# asincronico.net
KiCad netlist of a schematic drawn in Altium Designer
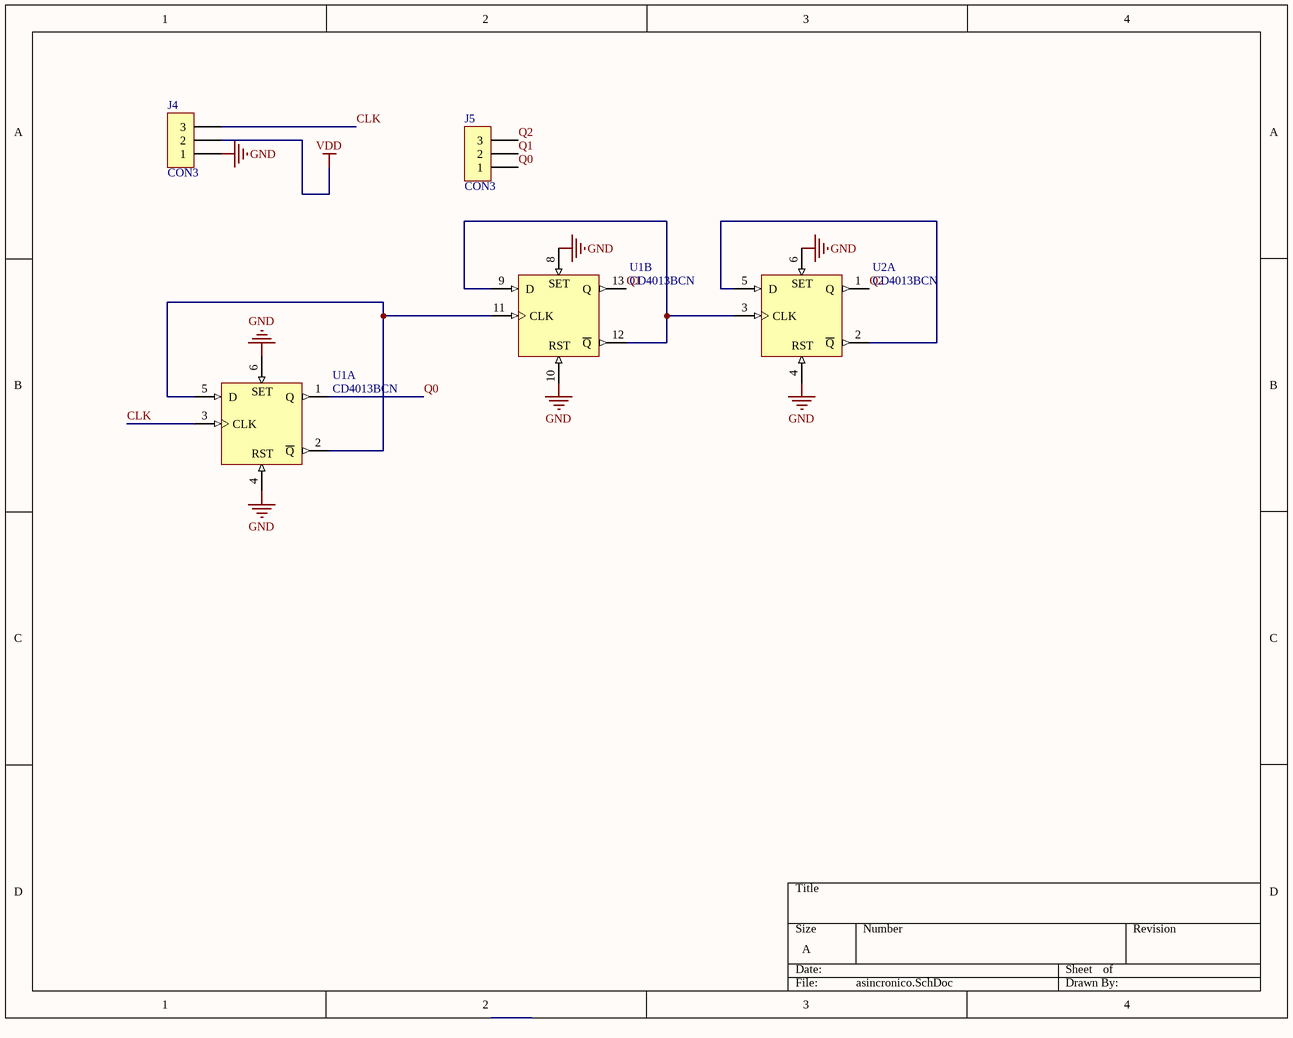
[diagram p0: asincronico.SchDoc]

(export (version "E")
  (design (tool "Eeschema 10.0.6"))
  (components
    (comp (ref "J4") (value "CON3") (footprint "SIP3") (libsource (lib "LIBEBAL") (part "CON3")))
    (comp (ref "J5") (value "CON3") (footprint "SIP3") (libsource (lib "LIBEBAL") (part "CON3")))
    (comp (ref "U1")
      (value "CD4013BCN")
      (footprint "N14A")
      (description "Dual D-Type Flip-Flop")
      (fields (field (name "PUBLISHER") "Altium Limited"))
      (libsource (lib "FSC Logic Flip-Flop") (part "CD4013BCN"))
    )
    (comp (ref "U2")
      (value "CD4013BCN")
      (footprint "N14A")
      (description "Dual D-Type Flip-Flop")
      (fields (field (name "PUBLISHER") "Altium Limited"))
      (libsource (lib "FSC Logic Flip-Flop") (part "CD4013BCN"))
    )
  )
  (nets
    (net (code "1") (name "/CLK") (class "Default")
      (node (ref "J4") (pin "3") (pinfunction "3_3") (pintype "passive"))
      (node (ref "U1") (pin "3") (pinfunction "CLK_3") (pintype "input"))
    )
    (net (code "2") (name "/Q0") (class "Default")
      (node (ref "J5") (pin "1") (pinfunction "1_1") (pintype "passive"))
      (node (ref "U1") (pin "1") (pinfunction "Q_1") (pintype "output"))
    )
    (net (code "3") (name "/Q1") (class "Default")
      (node (ref "J5") (pin "2") (pinfunction "2_2") (pintype "passive"))
      (node (ref "U1") (pin "13") (pinfunction "Q_13") (pintype "output"))
    )
    (net (code "4") (name "/Q2") (class "Default")
      (node (ref "J5") (pin "3") (pinfunction "3_3") (pintype "passive"))
      (node (ref "U2") (pin "1") (pinfunction "Q_1") (pintype "output"))
    )
    (net (code "5") (name "GND") (class "Default")
      (node (ref "J4") (pin "1") (pinfunction "1_1") (pintype "passive"))
      (node (ref "U1") (pin "10") (pinfunction "RST_10") (pintype "input"))
      (node (ref "U1") (pin "4") (pinfunction "RST_4") (pintype "input"))
      (node (ref "U1") (pin "6") (pinfunction "S_6") (pintype "input"))
      (node (ref "U1") (pin "7") (pinfunction "GND_7") (pintype "power_in"))
      (node (ref "U1") (pin "8") (pinfunction "S_8") (pintype "input"))
      (node (ref "U2") (pin "4") (pinfunction "RST_4") (pintype "input"))
      (node (ref "U2") (pin "6") (pinfunction "S_6") (pintype "input"))
      (node (ref "U2") (pin "7") (pinfunction "GND_7") (pintype "power_in"))
    )
    (net (code "6") (name "Net-(U1A-D)") (class "Default")
      (node (ref "U1") (pin "11") (pinfunction "CLK_11") (pintype "input"))
      (node (ref "U1") (pin "2") (pinfunction "~{Q}_2") (pintype "output"))
      (node (ref "U1") (pin "5") (pinfunction "D_5") (pintype "input"))
    )
    (net (code "7") (name "Net-(U1B-D)") (class "Default")
      (node (ref "U1") (pin "12") (pinfunction "~{Q}_12") (pintype "output"))
      (node (ref "U1") (pin "9") (pinfunction "D_9") (pintype "input"))
      (node (ref "U2") (pin "3") (pinfunction "CLK_3") (pintype "input"))
    )
    (net (code "8") (name "Net-(U2A-D)") (class "Default")
      (node (ref "U2") (pin "2") (pinfunction "~{Q}_2") (pintype "output"))
      (node (ref "U2") (pin "5") (pinfunction "D_5") (pintype "input"))
    )
    (net (code "9") (name "VDD") (class "Default")
      (node (ref "J4") (pin "2") (pinfunction "2_2") (pintype "passive"))
      (node (ref "U1") (pin "14") (pinfunction "VDD_14") (pintype "power_in"))
      (node (ref "U2") (pin "14") (pinfunction "VDD_14") (pintype "power_in"))
    )
  )
)
